# 1_5KbeaconDetectorV2_0.net
KiCad netlist of a schematic drawn in EAGLE
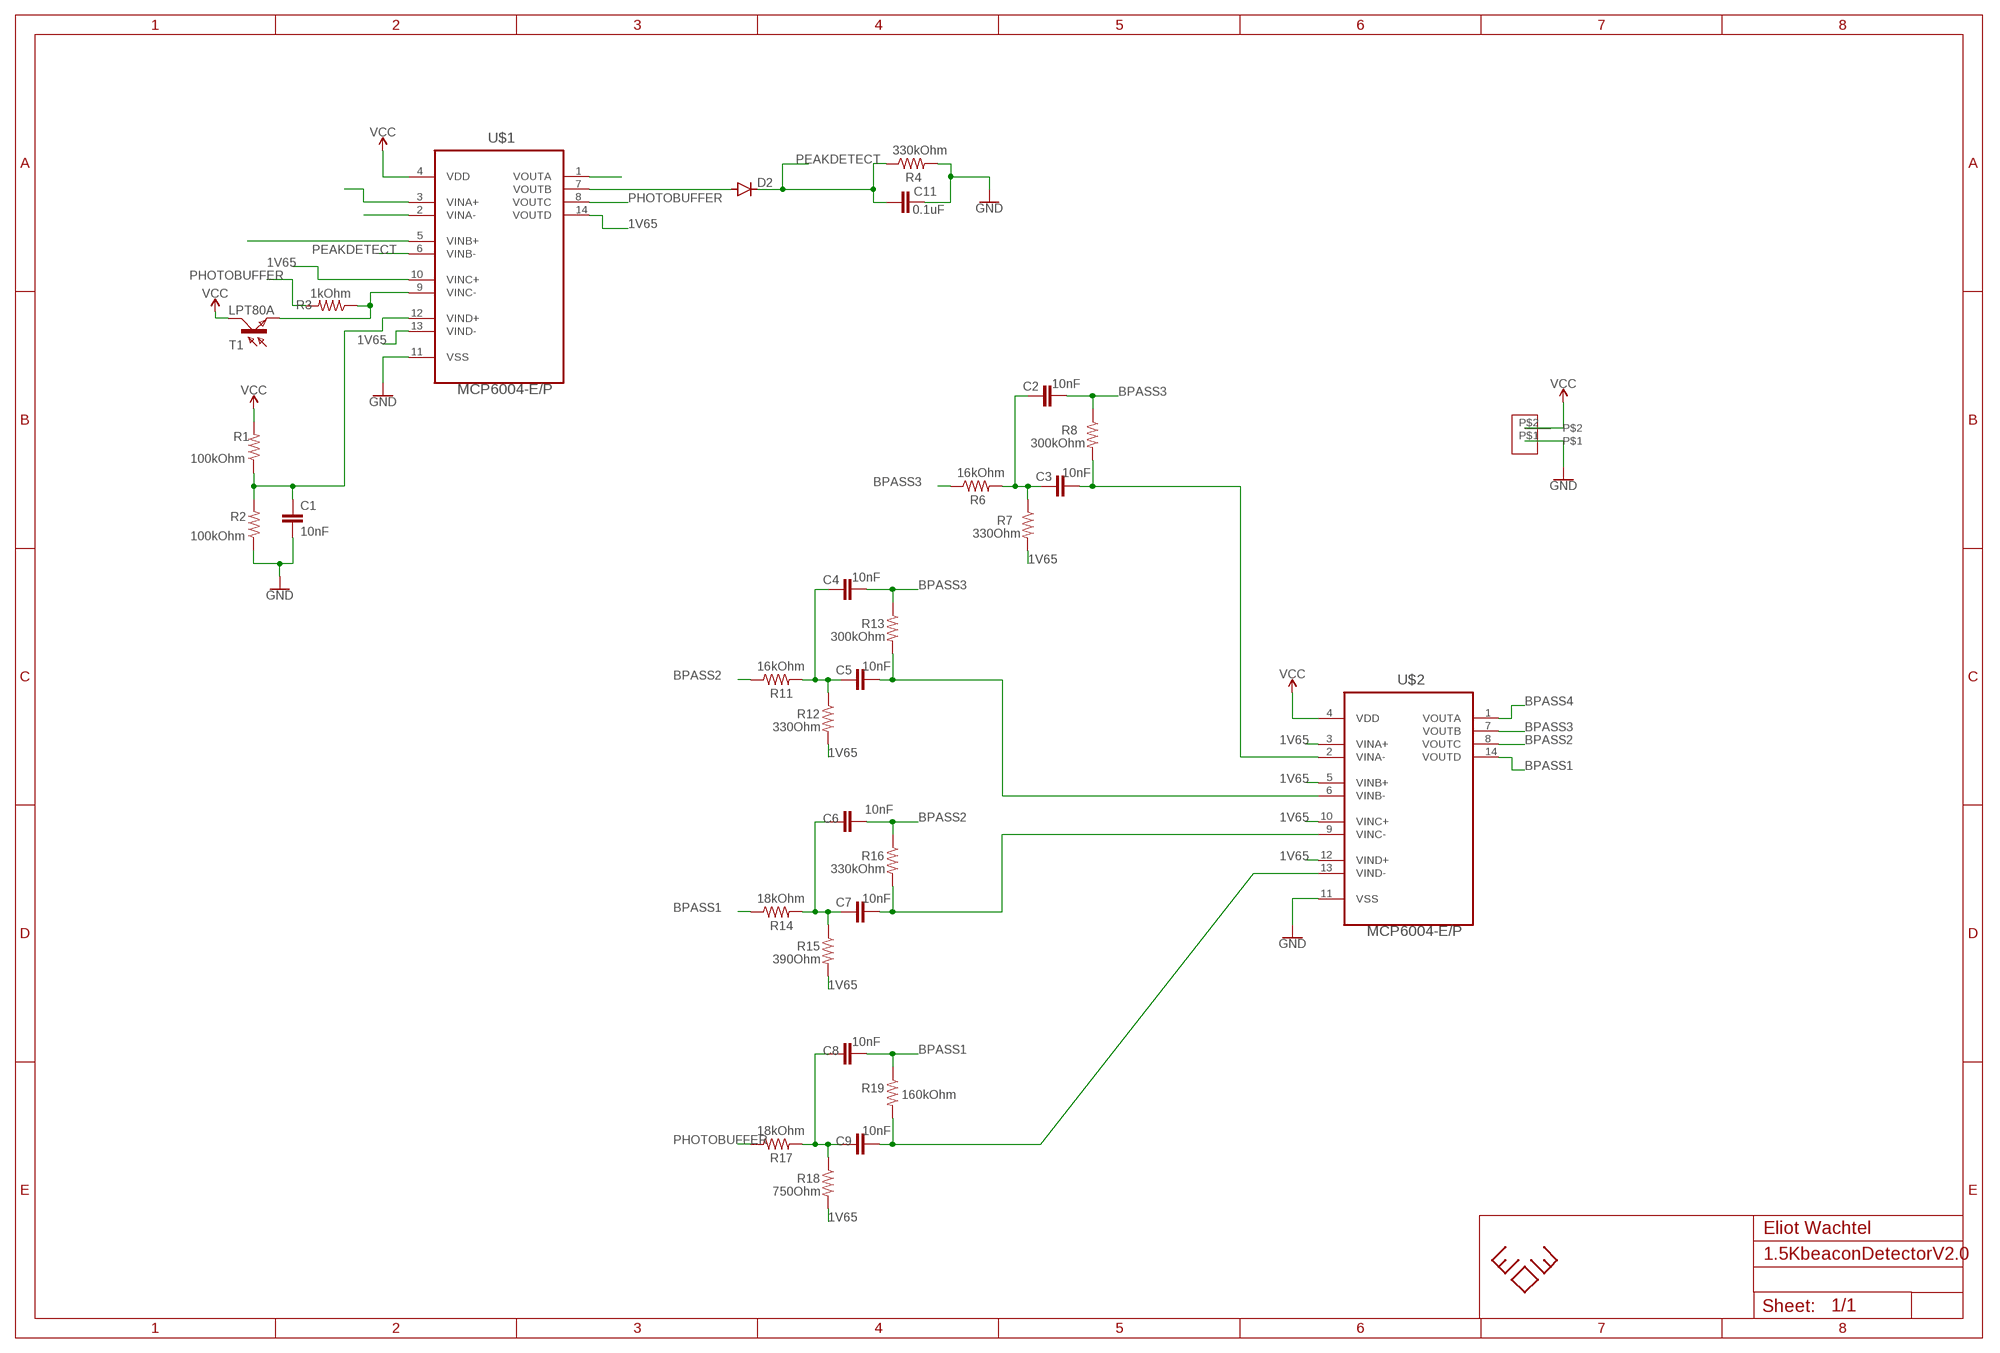
[diagram p0: schematic, sheet 1]

(export (version "E")
  (design (tool "Eeschema 10.0.6"))
  (components
    (comp (ref "C1")
      (value "10nF")
      (footprint "eagle-import:C5B2.5")
      (libsource (lib "eagle-import") (part "C5/2.5"))
    )
    (comp (ref "C2")
      (value "10nF")
      (footprint "eagle-import:C5B2.5")
      (libsource (lib "eagle-import") (part "C5/2.5"))
    )
    (comp (ref "C3")
      (value "10nF")
      (footprint "eagle-import:C5B2.5")
      (libsource (lib "eagle-import") (part "C5/2.5"))
    )
    (comp (ref "C4")
      (value "10nF")
      (footprint "eagle-import:C5B2.5")
      (libsource (lib "eagle-import") (part "C5/2.5"))
    )
    (comp (ref "C5")
      (value "10nF")
      (footprint "eagle-import:C5B2.5")
      (libsource (lib "eagle-import") (part "C5/2.5"))
    )
    (comp (ref "C6")
      (value "10nF")
      (footprint "eagle-import:C5B2.5")
      (libsource (lib "eagle-import") (part "C5/2.5"))
    )
    (comp (ref "C7")
      (value "10nF")
      (footprint "eagle-import:C5B2.5")
      (libsource (lib "eagle-import") (part "C5/2.5"))
    )
    (comp (ref "C8")
      (value "10nF")
      (footprint "eagle-import:C5B2.5")
      (libsource (lib "eagle-import") (part "C5/2.5"))
    )
    (comp (ref "C9")
      (value "10nF")
      (footprint "eagle-import:C5B2.5")
      (libsource (lib "eagle-import") (part "C5/2.5"))
    )
    (comp (ref "C11")
      (value "0.1uF")
      (footprint "eagle-import:C5B2.5")
      (libsource (lib "eagle-import") (part "C5/2.5"))
    )
    (comp (ref "D2")
      (value "DIODE-D-7.5")
      (footprint "eagle-import:D-7.5")
      (libsource (lib "eagle-import") (part "DIODE-D-7.5"))
    )
    (comp (ref "R1")
      (value "100kOhm")
      (footprint "eagle-import:0204_7")
      (libsource (lib "eagle-import") (part "R-US_0204/7"))
    )
    (comp (ref "R2")
      (value "100kOhm")
      (footprint "eagle-import:0204_7")
      (libsource (lib "eagle-import") (part "R-US_0204/7"))
    )
    (comp (ref "R3")
      (value "1kOhm")
      (footprint "eagle-import:0204V")
      (libsource (lib "eagle-import") (part "R-US_0204/2V"))
    )
    (comp (ref "R4")
      (value "330kOhm")
      (footprint "eagle-import:0204_5")
      (libsource (lib "eagle-import") (part "R-US_0204/5"))
    )
    (comp (ref "R6")
      (value "16kOhm")
      (footprint "eagle-import:0204V")
      (libsource (lib "eagle-import") (part "R-US_0204/2V"))
    )
    (comp (ref "R7")
      (value "330Ohm")
      (footprint "eagle-import:0204_7")
      (libsource (lib "eagle-import") (part "R-US_0204/7"))
    )
    (comp (ref "R8")
      (value "300kOhm")
      (footprint "eagle-import:0204_5")
      (libsource (lib "eagle-import") (part "R-US_0204/5"))
    )
    (comp (ref "R11")
      (value "16kOhm")
      (footprint "eagle-import:0204V")
      (libsource (lib "eagle-import") (part "R-US_0204/2V"))
    )
    (comp (ref "R12")
      (value "330Ohm")
      (footprint "eagle-import:0204_7")
      (libsource (lib "eagle-import") (part "R-US_0204/7"))
    )
    (comp (ref "R13")
      (value "300kOhm")
      (footprint "eagle-import:0204_5")
      (libsource (lib "eagle-import") (part "R-US_0204/5"))
    )
    (comp (ref "R14")
      (value "18kOhm")
      (footprint "eagle-import:0204_5")
      (libsource (lib "eagle-import") (part "R-US_0204/5"))
    )
    (comp (ref "R15")
      (value "390Ohm")
      (footprint "eagle-import:0204_7")
      (libsource (lib "eagle-import") (part "R-US_0204/7"))
    )
    (comp (ref "R16")
      (value "330kOhm")
      (footprint "eagle-import:0204_5")
      (libsource (lib "eagle-import") (part "R-US_0204/5"))
    )
    (comp (ref "R17")
      (value "18kOhm")
      (footprint "eagle-import:0204_5")
      (libsource (lib "eagle-import") (part "R-US_0204/5"))
    )
    (comp (ref "R18")
      (value "750Ohm")
      (footprint "eagle-import:0204_7")
      (libsource (lib "eagle-import") (part "R-US_0204/7"))
    )
    (comp (ref "R19")
      (value "160kOhm")
      (footprint "eagle-import:0204V")
      (libsource (lib "eagle-import") (part "R-US_0204/2V"))
    )
    (comp (ref "T1")
      (value "LPT80A")
      (footprint "eagle-import:LPT80A")
      (libsource (lib "eagle-import") (part "LPT80A"))
    )
    (comp (ref "U$1")
      (value "MCP6004-E/P")
      (footprint "eagle-import:DIP254P762X533-14")
      (fields
        (field (name "DIGI-KEY_PART_NUMBER") "MCP6004-E/P-ND")
        (field (name "MF") "Microchip Technology")
      )
      (libsource (lib "eagle-import") (part "MCP6004-E/P"))
    )
    (comp (ref "U$2")
      (value "MCP6004-E/P")
      (footprint "eagle-import:DIP254P762X533-14")
      (fields
        (field (name "DIGI-KEY_PART_NUMBER") "MCP6004-E/P-ND")
        (field (name "MF") "Microchip Technology")
      )
      (libsource (lib "eagle-import") (part "MCP6004-E/P"))
    )
    (comp (ref "U$4")
      (value "WIRECONNECT2PIN")
      (footprint "eagle-import:WIRECONNECT2PIN")
      (libsource (lib "eagle-import") (part "WIRECONNECT2PIN"))
    )
  )
  (nets
    (net (code "1") (name "/1V65") (class "Default")
      (node (ref "R12") (pin "2") (pinfunction "2_2") (pintype "passive"))
      (node (ref "R15") (pin "2") (pinfunction "2_2") (pintype "passive"))
      (node (ref "R18") (pin "2") (pinfunction "2_2") (pintype "passive"))
      (node (ref "R7") (pin "2") (pinfunction "2_2") (pintype "passive"))
      (node (ref "U$1") (pin "10") (pinfunction "VINC+_10") (pintype "input"))
      (node (ref "U$1") (pin "13") (pinfunction "VIND-_13") (pintype "input"))
      (node (ref "U$1") (pin "14") (pinfunction "VOUTD_14") (pintype "output"))
      (node (ref "U$2") (pin "10") (pinfunction "VINC+_10") (pintype "input"))
      (node (ref "U$2") (pin "12") (pinfunction "VIND+_12") (pintype "input"))
      (node (ref "U$2") (pin "3") (pinfunction "VINA+_3") (pintype "input"))
      (node (ref "U$2") (pin "5") (pinfunction "VINB+_5") (pintype "input"))
    )
    (net (code "2") (name "/BPASS1") (class "Default")
      (node (ref "C8") (pin "2") (pinfunction "2_2") (pintype "passive"))
      (node (ref "R14") (pin "1") (pinfunction "1_1") (pintype "passive"))
      (node (ref "R19") (pin "1") (pinfunction "1_1") (pintype "passive"))
      (node (ref "U$2") (pin "14") (pinfunction "VOUTD_14") (pintype "output"))
    )
    (net (code "3") (name "/BPASS2") (class "Default")
      (node (ref "C6") (pin "2") (pinfunction "2_2") (pintype "passive"))
      (node (ref "R11") (pin "1") (pinfunction "1_1") (pintype "passive"))
      (node (ref "R16") (pin "1") (pinfunction "1_1") (pintype "passive"))
      (node (ref "U$2") (pin "8") (pinfunction "VOUTC_8") (pintype "output"))
    )
    (net (code "4") (name "/BPASS3") (class "Default")
      (node (ref "C2") (pin "2") (pinfunction "2_2") (pintype "passive"))
      (node (ref "C4") (pin "2") (pinfunction "2_2") (pintype "passive"))
      (node (ref "R13") (pin "1") (pinfunction "1_1") (pintype "passive"))
      (node (ref "R6") (pin "1") (pinfunction "1_1") (pintype "passive"))
      (node (ref "R8") (pin "1") (pinfunction "1_1") (pintype "passive"))
      (node (ref "U$2") (pin "7") (pinfunction "VOUTB_7") (pintype "output"))
    )
    (net (code "5") (name "/BPASS4") (class "Default")
      (node (ref "U$2") (pin "1") (pinfunction "VOUTA_1") (pintype "output"))
    )
    (net (code "6") (name "/PEAKDETECT") (class "Default")
      (node (ref "C11") (pin "1") (pinfunction "1_1") (pintype "passive"))
      (node (ref "D2") (pin "C") (pinfunction "C_C") (pintype "passive"))
      (node (ref "R4") (pin "1") (pinfunction "1_1") (pintype "passive"))
      (node (ref "U$1") (pin "6") (pinfunction "VINB-_6") (pintype "input"))
    )
    (net (code "7") (name "/PHOTOBUFFER") (class "Default")
      (node (ref "R17") (pin "1") (pinfunction "1_1") (pintype "passive"))
      (node (ref "R3") (pin "2") (pinfunction "2_2") (pintype "passive"))
      (node (ref "U$1") (pin "8") (pinfunction "VOUTC_8") (pintype "output"))
    )
    (net (code "8") (name "GND") (class "Default")
      (node (ref "C1") (pin "2") (pinfunction "2_2") (pintype "passive"))
      (node (ref "C11") (pin "2") (pinfunction "2_2") (pintype "passive"))
      (node (ref "R2") (pin "1") (pinfunction "1_1") (pintype "passive"))
      (node (ref "R4") (pin "2") (pinfunction "2_2") (pintype "passive"))
      (node (ref "U$1") (pin "11") (pinfunction "VSS_11") (pintype "power_in"))
      (node (ref "U$2") (pin "11") (pinfunction "VSS_11") (pintype "power_in"))
      (node (ref "U$4") (pin "P$1") (pinfunction "P$1_P$1") (pintype "bidirectional"))
    )
    (net (code "9") (name "Net-(C2-Pad1)") (class "Default")
      (node (ref "C2") (pin "1") (pinfunction "1_1") (pintype "passive"))
      (node (ref "C3") (pin "1") (pinfunction "1_1") (pintype "passive"))
      (node (ref "R6") (pin "2") (pinfunction "2_2") (pintype "passive"))
      (node (ref "R7") (pin "1") (pinfunction "1_1") (pintype "passive"))
    )
    (net (code "10") (name "Net-(C4-Pad1)") (class "Default")
      (node (ref "C4") (pin "1") (pinfunction "1_1") (pintype "passive"))
      (node (ref "C5") (pin "1") (pinfunction "1_1") (pintype "passive"))
      (node (ref "R11") (pin "2") (pinfunction "2_2") (pintype "passive"))
      (node (ref "R12") (pin "1") (pinfunction "1_1") (pintype "passive"))
    )
    (net (code "11") (name "Net-(C6-Pad1)") (class "Default")
      (node (ref "C6") (pin "1") (pinfunction "1_1") (pintype "passive"))
      (node (ref "C7") (pin "1") (pinfunction "1_1") (pintype "passive"))
      (node (ref "R14") (pin "2") (pinfunction "2_2") (pintype "passive"))
      (node (ref "R15") (pin "1") (pinfunction "1_1") (pintype "passive"))
    )
    (net (code "12") (name "Net-(C8-Pad1)") (class "Default")
      (node (ref "C8") (pin "1") (pinfunction "1_1") (pintype "passive"))
      (node (ref "C9") (pin "1") (pinfunction "1_1") (pintype "passive"))
      (node (ref "R17") (pin "2") (pinfunction "2_2") (pintype "passive"))
      (node (ref "R18") (pin "1") (pinfunction "1_1") (pintype "passive"))
    )
    (net (code "13") (name "Net-(U$1-VINC-)") (class "Default")
      (node (ref "R3") (pin "1") (pinfunction "1_1") (pintype "passive"))
      (node (ref "T1") (pin "E") (pinfunction "E_E") (pintype "passive"))
      (node (ref "U$1") (pin "9") (pinfunction "VINC-_9") (pintype "input"))
    )
    (net (code "14") (name "Net-(U$1-VIND+)") (class "Default")
      (node (ref "C1") (pin "1") (pinfunction "1_1") (pintype "passive"))
      (node (ref "R1") (pin "1") (pinfunction "1_1") (pintype "passive"))
      (node (ref "R2") (pin "2") (pinfunction "2_2") (pintype "passive"))
      (node (ref "U$1") (pin "12") (pinfunction "VIND+_12") (pintype "input"))
    )
    (net (code "15") (name "Net-(U$1-VOUTB)") (class "Default")
      (node (ref "D2") (pin "A") (pinfunction "A_A") (pintype "passive"))
      (node (ref "U$1") (pin "7") (pinfunction "VOUTB_7") (pintype "output"))
    )
    (net (code "16") (name "Net-(U$2-VINA-)") (class "Default")
      (node (ref "C3") (pin "2") (pinfunction "2_2") (pintype "passive"))
      (node (ref "R8") (pin "2") (pinfunction "2_2") (pintype "passive"))
      (node (ref "U$2") (pin "2") (pinfunction "VINA-_2") (pintype "input"))
    )
    (net (code "17") (name "Net-(U$2-VINB-)") (class "Default")
      (node (ref "C5") (pin "2") (pinfunction "2_2") (pintype "passive"))
      (node (ref "R13") (pin "2") (pinfunction "2_2") (pintype "passive"))
      (node (ref "U$2") (pin "6") (pinfunction "VINB-_6") (pintype "input"))
    )
    (net (code "18") (name "Net-(U$2-VINC-)") (class "Default")
      (node (ref "C7") (pin "2") (pinfunction "2_2") (pintype "passive"))
      (node (ref "R16") (pin "2") (pinfunction "2_2") (pintype "passive"))
      (node (ref "U$2") (pin "9") (pinfunction "VINC-_9") (pintype "input"))
    )
    (net (code "19") (name "Net-(U$2-VIND-)") (class "Default")
      (node (ref "C9") (pin "2") (pinfunction "2_2") (pintype "passive"))
      (node (ref "R19") (pin "2") (pinfunction "2_2") (pintype "passive"))
      (node (ref "U$2") (pin "13") (pinfunction "VIND-_13") (pintype "input"))
    )
    (net (code "20") (name "VCC") (class "Default")
      (node (ref "R1") (pin "2") (pinfunction "2_2") (pintype "passive"))
      (node (ref "T1") (pin "C") (pinfunction "C_C") (pintype "passive"))
      (node (ref "U$1") (pin "4") (pinfunction "VDD_4") (pintype "power_in"))
      (node (ref "U$2") (pin "4") (pinfunction "VDD_4") (pintype "power_in"))
      (node (ref "U$4") (pin "P$2") (pinfunction "P$2_P$2") (pintype "bidirectional"))
    )
    (net (code "21") (name "unconnected-(U$1-VINA+-Pad3)") (class "Default")
      (node (ref "U$1") (pin "3") (pinfunction "VINA+_3") (pintype "input"))
    )
    (net (code "22") (name "unconnected-(U$1-VINA--Pad2)") (class "Default")
      (node (ref "U$1") (pin "2") (pinfunction "VINA-_2") (pintype "input"))
    )
    (net (code "23") (name "unconnected-(U$1-VINB+-Pad5)") (class "Default")
      (node (ref "U$1") (pin "5") (pinfunction "VINB+_5") (pintype "input"))
    )
    (net (code "24") (name "unconnected-(U$1-VOUTA-Pad1)") (class "Default")
      (node (ref "U$1") (pin "1") (pinfunction "VOUTA_1") (pintype "output"))
    )
  )
)
